# TapuinoMini.net
KiCad netlist of a schematic drawn in EAGLE
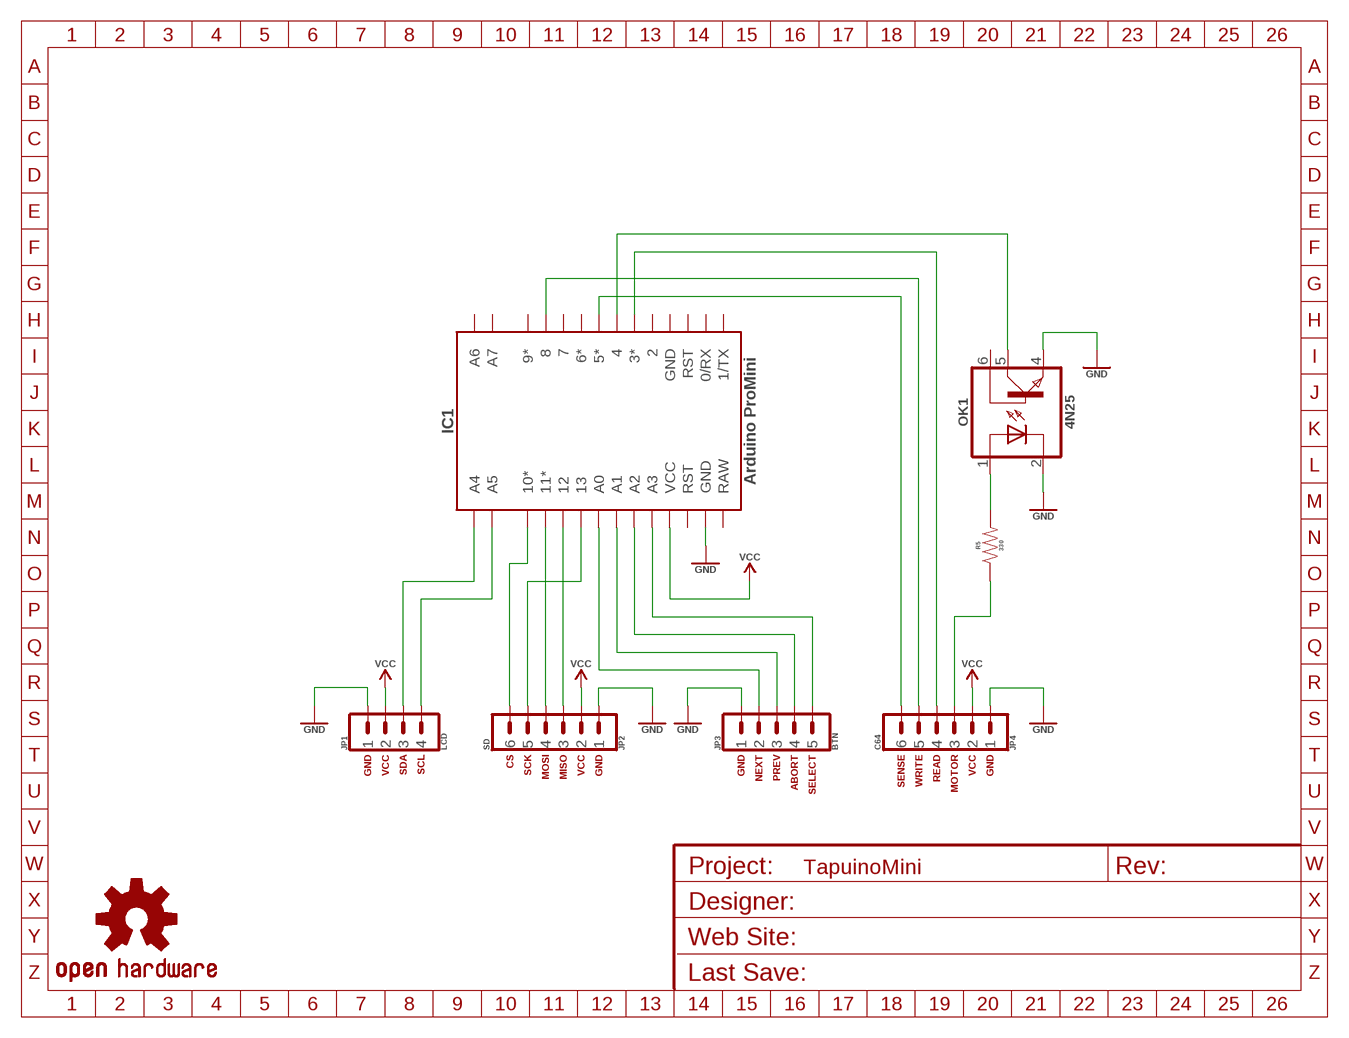
[diagram p0: schematic, sheet 1]

(export (version "E")
  (design (tool "Eeschema 10.0.6"))
  (components
    (comp (ref "IC1")
      (value "Arduino ProMini")
      (footprint "eagle-import:PROMINI_A")
      (libsource (lib "eagle-import") (part "PROMINI_A"))
    )
    (comp (ref "JP1")
      (value "LCD")
      (footprint "eagle-import:1X04_SQR")
      (libsource (lib "eagle-import") (part "1X04_SQR"))
    )
    (comp (ref "JP2")
      (value "SD")
      (footprint "eagle-import:1X06_SQR")
      (libsource (lib "eagle-import") (part "1X06_SQR"))
    )
    (comp (ref "JP3")
      (value "BTN")
      (footprint "eagle-import:1X05_SQR")
      (libsource (lib "eagle-import") (part "1X05_SQR"))
    )
    (comp (ref "JP4")
      (value "C64")
      (footprint "eagle-import:1X06_SQR")
      (libsource (lib "eagle-import") (part "1X06_SQR"))
    )
    (comp (ref "LOGO1")
      (value "OSHW-LOGOL")
      (footprint "eagle-import:OSHW-LOGO-L")
      (libsource (lib "eagle-import") (part "OSHW-LOGOL"))
    )
    (comp (ref "OK1")
      (value "4N25")
      (footprint "eagle-import:DIP06")
      (libsource (lib "eagle-import") (part "OPTO_6PIN_4NXX"))
    )
    (comp (ref "R5")
      (value "330")
      (footprint "eagle-import:RESISTOR_PTH_0.3")
      (libsource (lib "eagle-import") (part "RESISTOR_PTH_0.3"))
    )
  )
  (nets
    (net (code "1") (name "GND") (class "Default")
      (node (ref "IC1") (pin "GND@1") (pinfunction "GND_GND@1") (pintype "bidirectional"))
      (node (ref "JP1") (pin "1") (pinfunction "1_1") (pintype "passive"))
      (node (ref "JP2") (pin "1") (pinfunction "1_1") (pintype "passive"))
      (node (ref "JP3") (pin "1") (pinfunction "1_1") (pintype "passive"))
      (node (ref "JP4") (pin "1") (pinfunction "1_1") (pintype "passive"))
      (node (ref "OK1") (pin "2") (pinfunction "CATHODE_2") (pintype "passive"))
      (node (ref "OK1") (pin "4") (pinfunction "EMITTER_4") (pintype "passive"))
    )
    (net (code "2") (name "Net-(IC1-Pad3*)") (class "Default")
      (node (ref "IC1") (pin "3*") (pinfunction "3*_3*") (pintype "bidirectional"))
      (node (ref "JP4") (pin "4") (pinfunction "4_4") (pintype "passive"))
    )
    (net (code "3") (name "Net-(IC1-Pad5*)") (class "Default")
      (node (ref "IC1") (pin "5*") (pinfunction "5*_5*") (pintype "bidirectional"))
      (node (ref "JP4") (pin "6") (pinfunction "6_6") (pintype "passive"))
    )
    (net (code "4") (name "Net-(IC1-Pad8)") (class "Default")
      (node (ref "IC1") (pin "8") (pinfunction "8_8") (pintype "bidirectional"))
      (node (ref "JP4") (pin "5") (pinfunction "5_5") (pintype "passive"))
    )
    (net (code "5") (name "Net-(IC1-Pad10*)") (class "Default")
      (node (ref "IC1") (pin "10*") (pinfunction "10*_10*") (pintype "bidirectional"))
      (node (ref "JP2") (pin "6") (pinfunction "6_6") (pintype "passive"))
    )
    (net (code "6") (name "Net-(IC1-Pad11*)") (class "Default")
      (node (ref "IC1") (pin "11*") (pinfunction "11*_11*") (pintype "bidirectional"))
      (node (ref "JP2") (pin "4") (pinfunction "4_4") (pintype "passive"))
    )
    (net (code "7") (name "Net-(IC1-Pad12)") (class "Default")
      (node (ref "IC1") (pin "12") (pinfunction "12_12") (pintype "bidirectional"))
      (node (ref "JP2") (pin "3") (pinfunction "3_3") (pintype "passive"))
    )
    (net (code "8") (name "Net-(IC1-Pad13)") (class "Default")
      (node (ref "IC1") (pin "13") (pinfunction "13_13") (pintype "bidirectional"))
      (node (ref "JP2") (pin "5") (pinfunction "5_5") (pintype "passive"))
    )
    (net (code "9") (name "Net-(IC1-PadA0)") (class "Default")
      (node (ref "IC1") (pin "A0") (pinfunction "A0_A0") (pintype "bidirectional"))
      (node (ref "JP3") (pin "2") (pinfunction "2_2") (pintype "passive"))
    )
    (net (code "10") (name "Net-(IC1-PadA1)") (class "Default")
      (node (ref "IC1") (pin "A1") (pinfunction "A1_A1") (pintype "bidirectional"))
      (node (ref "JP3") (pin "3") (pinfunction "3_3") (pintype "passive"))
    )
    (net (code "11") (name "Net-(IC1-PadA2)") (class "Default")
      (node (ref "IC1") (pin "A2") (pinfunction "A2_A2") (pintype "bidirectional"))
      (node (ref "JP3") (pin "4") (pinfunction "4_4") (pintype "passive"))
    )
    (net (code "12") (name "Net-(IC1-PadA3)") (class "Default")
      (node (ref "IC1") (pin "A3") (pinfunction "A3_A3") (pintype "bidirectional"))
      (node (ref "JP3") (pin "5") (pinfunction "5_5") (pintype "passive"))
    )
    (net (code "13") (name "Net-(IC1-PadA4)") (class "Default")
      (node (ref "IC1") (pin "A4") (pinfunction "A4_A4") (pintype "bidirectional"))
      (node (ref "JP1") (pin "3") (pinfunction "3_3") (pintype "passive"))
    )
    (net (code "14") (name "Net-(IC1-PadA5)") (class "Default")
      (node (ref "IC1") (pin "A5") (pinfunction "A5_A5") (pintype "bidirectional"))
      (node (ref "JP1") (pin "4") (pinfunction "4_4") (pintype "passive"))
    )
    (net (code "15") (name "Net-(JP4-Pad3)") (class "Default")
      (node (ref "JP4") (pin "3") (pinfunction "3_3") (pintype "passive"))
      (node (ref "R5") (pin "1") (pinfunction "1_1") (pintype "passive"))
    )
    (net (code "16") (name "Net-(OK1-ANODE)") (class "Default")
      (node (ref "OK1") (pin "1") (pinfunction "ANODE_1") (pintype "passive"))
      (node (ref "R5") (pin "2") (pinfunction "2_2") (pintype "passive"))
    )
    (net (code "17") (name "Net-(OK1-COLLECTOR)") (class "Default")
      (node (ref "IC1") (pin "4") (pinfunction "4_4") (pintype "bidirectional"))
      (node (ref "OK1") (pin "5") (pinfunction "COLLECTOR_5") (pintype "passive"))
    )
    (net (code "18") (name "VCC") (class "Default")
      (node (ref "IC1") (pin "VCC") (pinfunction "VCC_VCC") (pintype "bidirectional"))
      (node (ref "JP1") (pin "2") (pinfunction "2_2") (pintype "passive"))
      (node (ref "JP2") (pin "2") (pinfunction "2_2") (pintype "passive"))
      (node (ref "JP4") (pin "2") (pinfunction "2_2") (pintype "passive"))
    )
    (net (code "19") (name "unconnected-(IC1-GND-PadGND@2)") (class "Default")
      (node (ref "IC1") (pin "GND@2") (pinfunction "GND_GND@2") (pintype "bidirectional"))
    )
    (net (code "20") (name "unconnected-(IC1-Pad0{slash}RX)") (class "Default")
      (node (ref "IC1") (pin "0/RX") (pinfunction "0/RX_0/RX") (pintype "bidirectional"))
    )
    (net (code "21") (name "unconnected-(IC1-Pad1{slash}TX)") (class "Default")
      (node (ref "IC1") (pin "1/TX") (pinfunction "1/TX_1/TX") (pintype "bidirectional"))
    )
    (net (code "22") (name "unconnected-(IC1-Pad2)") (class "Default")
      (node (ref "IC1") (pin "2") (pinfunction "2_2") (pintype "bidirectional"))
    )
    (net (code "23") (name "unconnected-(IC1-Pad6*)") (class "Default")
      (node (ref "IC1") (pin "6*") (pinfunction "6*_6*") (pintype "bidirectional"))
    )
    (net (code "24") (name "unconnected-(IC1-Pad7)") (class "Default")
      (node (ref "IC1") (pin "7") (pinfunction "7_7") (pintype "bidirectional"))
    )
    (net (code "25") (name "unconnected-(IC1-Pad9*)") (class "Default")
      (node (ref "IC1") (pin "9*") (pinfunction "9*_9*") (pintype "bidirectional"))
    )
    (net (code "26") (name "unconnected-(IC1-PadA6)") (class "Default")
      (node (ref "IC1") (pin "A6") (pinfunction "A6_A6") (pintype "bidirectional"))
    )
    (net (code "27") (name "unconnected-(IC1-PadA7)") (class "Default")
      (node (ref "IC1") (pin "A7") (pinfunction "A7_A7") (pintype "bidirectional"))
    )
    (net (code "28") (name "unconnected-(IC1-PadRAW)") (class "Default")
      (node (ref "IC1") (pin "RAW") (pinfunction "RAW_RAW") (pintype "bidirectional"))
    )
    (net (code "29") (name "unconnected-(IC1-RST-PadRST@1)") (class "Default")
      (node (ref "IC1") (pin "RST@1") (pinfunction "RST_RST@1") (pintype "bidirectional"))
    )
    (net (code "30") (name "unconnected-(IC1-RST-PadRST@2)") (class "Default")
      (node (ref "IC1") (pin "RST@2") (pinfunction "RST_RST@2") (pintype "bidirectional"))
    )
    (net (code "31") (name "unconnected-(OK1-BASE-Pad6)") (class "Default")
      (node (ref "OK1") (pin "6") (pinfunction "BASE_6") (pintype "passive"))
    )
  )
)
